# sheet_LAC.net
KiCad netlist of a schematic drawn in Altium Designer
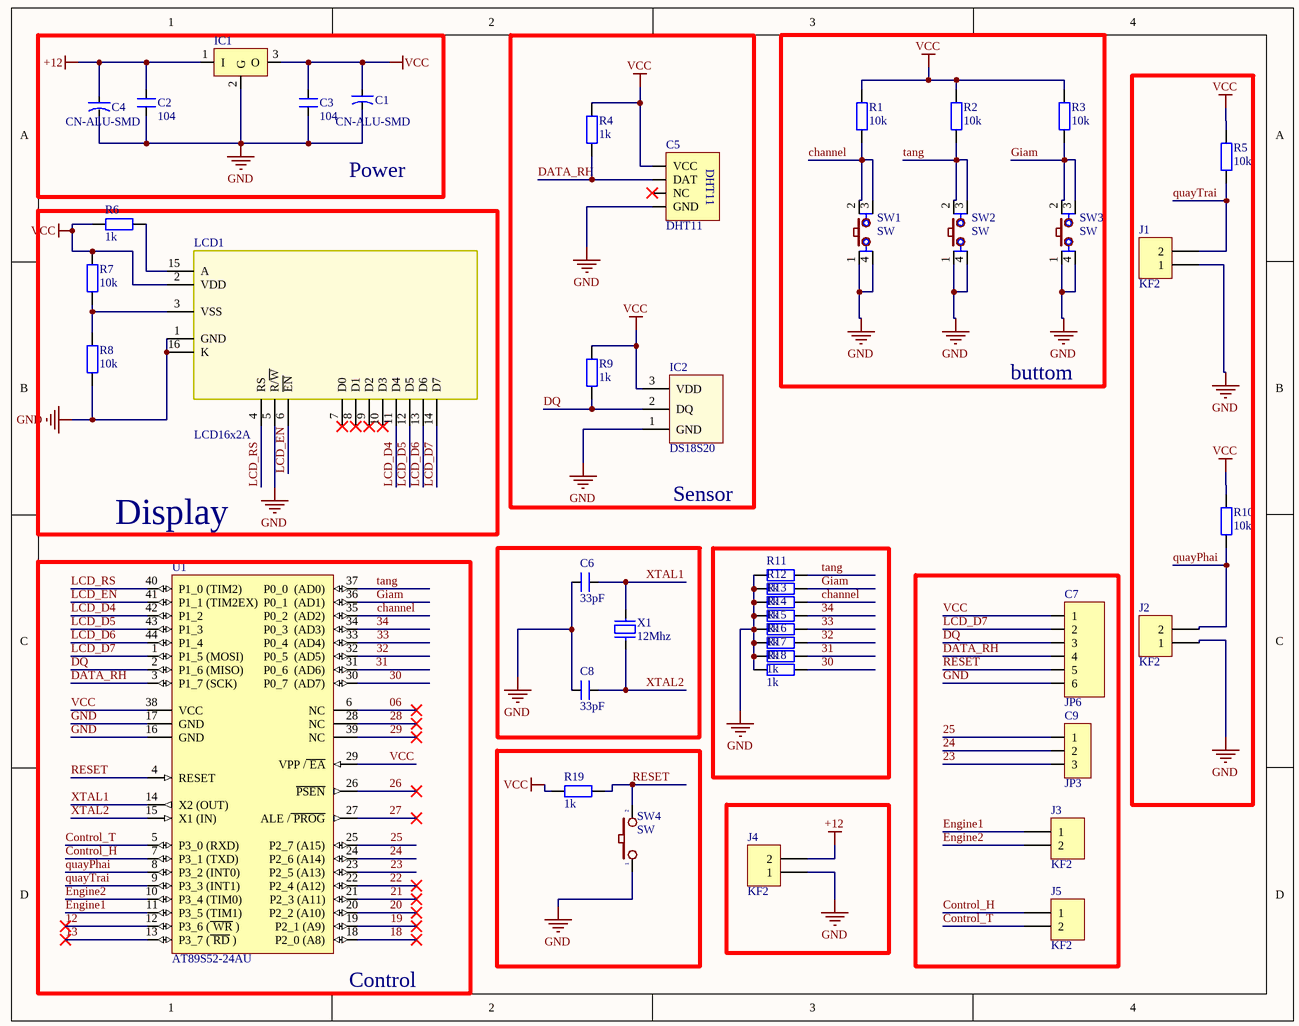
[diagram p0: sheet_LAC.SchDoc]

(export (version "E")
  (design (tool "Eeschema 10.0.6"))
  (components
    (comp (ref "C1")
      (value "CN-ALU-SMD")
      (footprint "3.2X1.6X1.1")
      (description "Polarized Capacitor (Axial)")
      (fields (field (name "PUBLISHER") "Altium Limited"))
      (libsource (lib "LIBRARY") (part "CN-ALU-SMD"))
    )
    (comp (ref "C2")
      (value "104")
      (footprint "SM-CAP-0805")
      (fields (field (name "DESIGNED BY") "VanDungEvn"))
      (libsource (lib "syhaunguyen") (part "CN"))
    )
    (comp (ref "C3")
      (value "104")
      (footprint "SM-CAP-0805")
      (fields (field (name "DESIGNED BY") "VanDungEvn"))
      (libsource (lib "syhaunguyen") (part "CN"))
    )
    (comp (ref "C4")
      (value "CN-ALU-SMD")
      (footprint "3.2X1.6X1.1")
      (description "Polarized Capacitor (Axial)")
      (fields (field (name "PUBLISHER") "Altium Limited"))
      (libsource (lib "LIBRARY") (part "CN-ALU-SMD"))
    )
    (comp (ref "C5")
      (value "DHT11")
      (footprint "DHT11")
      (fields
        (field (name "MANUFACTURER") "Würth Elektronik eiSos GmbH")
        (field (name "PARTNO") "613004143121")
        (field (name "CREATED BY") "Karrer Zheng")
      )
      (libsource (lib "LIBRARY") (part "DHT11"))
    )
    (comp (ref "C6")
      (value "33pF")
      (footprint "6-0805_N")
      (description "Cap np  1pF - 472pF")
      (libsource (lib "syhaunguyen") (part "CN1"))
    )
    (comp (ref "C7")
      (value "JP6")
      (footprint "JP6-C1T")
      (description "WR-PHD 2.54 mm Angled Socket Header")
      (fields
        (field (name "MANUFACTURER") "Würth Elektronik eiSos GmbH")
        (field (name "PARTNO") "613006143121")
        (field (name "CREATED BY") "Karrer Zheng")
      )
      (libsource (lib "LIBRARY") (part "JP6"))
    )
    (comp (ref "C8")
      (value "33pF")
      (footprint "6-0805_N")
      (description "Cap np  1pF - 472pF")
      (libsource (lib "syhaunguyen") (part "CN1"))
    )
    (comp (ref "C9")
      (value "JP3")
      (footprint "JP3-C1T")
      (description "WR-PHD 2.54 mm Angled Socket Header")
      (fields
        (field (name "MANUFACTURER") "Würth Elektronik eiSos GmbH")
        (field (name "PARTNO") "613003143121")
        (field (name "CREATED BY") "Karrer Zheng")
      )
      (libsource (lib "LIBRARY") (part "JP3"))
    )
    (comp (ref "IC1")
      (value "LM78xx")
      (footprint "TO252-123")
      (description "Positive Voltage Regulator")
      (fields (field (name "PUBLISHER") "Altium Limited"))
      (libsource (lib "LIBRARY") (part "LM78xx"))
    )
    (comp (ref "IC2")
      (value "DS18S20")
      (footprint "JP3-C1T")
      (description "High Precision  1-Wire® Digital Thermometer")
      (libsource (lib "LIBRARY") (part "DS18S20"))
    )
    (comp (ref "J1")
      (value "KF2")
      (footprint "KF2-3.5")
      (fields
        (field (name "MANUFACTURER") "Würth Elektronik eiSos GmbH")
        (field (name "PARTNO") "691103110002")
        (field (name "CREATED BY") "Karrer Zheng")
      )
      (libsource (lib "") (part "KF2_1"))
    )
    (comp (ref "J2")
      (value "KF2")
      (footprint "KF2-3.5")
      (fields
        (field (name "MANUFACTURER") "Würth Elektronik eiSos GmbH")
        (field (name "PARTNO") "691103110002")
        (field (name "CREATED BY") "Karrer Zheng")
      )
      (libsource (lib "") (part "KF2_1"))
    )
    (comp (ref "J3")
      (value "KF2")
      (footprint "KF2-3.5")
      (fields
        (field (name "MANUFACTURER") "Würth Elektronik eiSos GmbH")
        (field (name "PARTNO") "691103110002")
        (field (name "CREATED BY") "Karrer Zheng")
      )
      (libsource (lib "LIBRARY") (part "KF2"))
    )
    (comp (ref "J4")
      (value "KF2")
      (footprint "KF2-5.08")
      (fields
        (field (name "MANUFACTURER") "Würth Elektronik eiSos GmbH")
        (field (name "PARTNO") "691103110002")
        (field (name "CREATED BY") "Karrer Zheng")
      )
      (libsource (lib "") (part "KF2_1"))
    )
    (comp (ref "J5")
      (value "KF2")
      (footprint "KF2-3.5")
      (fields
        (field (name "MANUFACTURER") "Würth Elektronik eiSos GmbH")
        (field (name "PARTNO") "691103110002")
        (field (name "CREATED BY") "Karrer Zheng")
      )
      (libsource (lib "LIBRARY") (part "KF2"))
    )
    (comp (ref "LCD1")
      (value "LCD16x2A")
      (footprint "LCD16X2")
      (description "LCD dipslay 16 char, 2 line")
      (libsource (lib "syhaunguyen") (part "LCD16x2"))
    )
    (comp (ref "R1")
      (value "10k")
      (footprint "6-0805_N")
      (description "Resistor 1/4W")
      (libsource (lib "syhaunguyen") (part "R1/4W"))
    )
    (comp (ref "R2")
      (value "10k")
      (footprint "6-0805_N")
      (description "Resistor 1/4W")
      (libsource (lib "syhaunguyen") (part "R1/4W"))
    )
    (comp (ref "R3")
      (value "10k")
      (footprint "6-0805_N")
      (description "Resistor 1/4W")
      (libsource (lib "syhaunguyen") (part "R1/4W"))
    )
    (comp (ref "R4")
      (value "1k")
      (footprint "6-0805_N")
      (description "Resistor 1/4W")
      (libsource (lib "syhaunguyen") (part "R1/4W"))
    )
    (comp (ref "R5")
      (value "10k")
      (footprint "6-0805_N")
      (description "Resistor 1/4W")
      (libsource (lib "syhaunguyen") (part "R1/4W"))
    )
    (comp (ref "R6")
      (value "1k")
      (footprint "6-0805_N")
      (description "Resistor 1/4W")
      (libsource (lib "syhaunguyen") (part "R1/4W"))
    )
    (comp (ref "R7")
      (value "10k")
      (footprint "6-0805_N")
      (description "Resistor 1/4W")
      (libsource (lib "syhaunguyen") (part "R1/4W"))
    )
    (comp (ref "R8")
      (value "10k")
      (footprint "6-0805_N")
      (description "Resistor 1/4W")
      (libsource (lib "syhaunguyen") (part "R1/4W"))
    )
    (comp (ref "R9")
      (value "1k")
      (footprint "6-0805_N")
      (description "Resistor 1/4W")
      (libsource (lib "syhaunguyen") (part "R1/4W"))
    )
    (comp (ref "R10")
      (value "10k")
      (footprint "6-0805_N")
      (description "Resistor 1/4W")
      (libsource (lib "syhaunguyen") (part "R1/4W"))
    )
    (comp (ref "R11")
      (value "1k")
      (footprint "6-0805_N")
      (description "Resistor 1/4W")
      (libsource (lib "syhaunguyen") (part "R1/4W"))
    )
    (comp (ref "R12")
      (value "1k")
      (footprint "6-0805_N")
      (description "Resistor 1/4W")
      (libsource (lib "syhaunguyen") (part "R1/4W"))
    )
    (comp (ref "R13")
      (value "1k")
      (footprint "6-0805_N")
      (description "Resistor 1/4W")
      (libsource (lib "syhaunguyen") (part "R1/4W"))
    )
    (comp (ref "R14")
      (value "1k")
      (footprint "6-0805_N")
      (description "Resistor 1/4W")
      (libsource (lib "syhaunguyen") (part "R1/4W"))
    )
    (comp (ref "R15")
      (value "1k")
      (footprint "6-0805_N")
      (description "Resistor 1/4W")
      (libsource (lib "syhaunguyen") (part "R1/4W"))
    )
    (comp (ref "R16")
      (value "1k")
      (footprint "6-0805_N")
      (description "Resistor 1/4W")
      (libsource (lib "syhaunguyen") (part "R1/4W"))
    )
    (comp (ref "R17")
      (value "1k")
      (footprint "6-0805_N")
      (description "Resistor 1/4W")
      (libsource (lib "syhaunguyen") (part "R1/4W"))
    )
    (comp (ref "R18")
      (value "1k")
      (footprint "6-0805_N")
      (description "Resistor 1/4W")
      (libsource (lib "syhaunguyen") (part "R1/4W"))
    )
    (comp (ref "R19")
      (value "1k")
      (footprint "6-0805_N")
      (description "Resistor 1/4W")
      (libsource (lib "syhaunguyen") (part "R1/4W"))
    )
    (comp (ref "SW1")
      (value "SW")
      (footprint "SW2-DIP")
      (description "Switch button 4 pin")
      (libsource (lib "LIBRARY") (part "SW4"))
    )
    (comp (ref "SW2")
      (value "SW")
      (footprint "SW2-DIP")
      (description "Switch button 4 pin")
      (libsource (lib "LIBRARY") (part "SW4"))
    )
    (comp (ref "SW3")
      (value "SW")
      (footprint "SW2-DIP")
      (description "Switch button 4 pin")
      (libsource (lib "LIBRARY") (part "SW4"))
    )
    (comp (ref "SW4")
      (value "SW")
      (footprint "SW1-SMD")
      (description "Switch button 2 pin")
      (libsource (lib "LIBRARY") (part "SW2"))
    )
    (comp (ref "U1")
      (value "AT89S52-24AU")
      (footprint "TQFP44")
      (description "Atmel 8 Bit Micro 4.0-5.5V 24MHz -40 to +80 Deg C 44TQFP (44A) Package GREEN OPTION")
      (libsource (lib "LIBRARY") (part "AT89S52-24AU"))
    )
    (comp (ref "X1")
      (value "12Mhz")
      (footprint "XT2-SMD")
      (description "Crystal, 32.768 KHz, -40 to 85 degC, 3.2 x 1.5 x 0.9 mm SMD")
      (libsource (lib "LIBRARY") (part "XT2"))
    )
  )
  (nets
    (net (code "1") (name "+12") (class "Default")
      (node (ref "C2") (pin "1") (pinfunction "1_1") (pintype "passive"))
      (node (ref "C4") (pin "1") (pinfunction "1_1") (pintype "passive"))
      (node (ref "IC1") (pin "1") (pinfunction "I_1") (pintype "power_in"))
      (node (ref "J4") (pin "2") (pinfunction "2_2") (pintype "passive"))
    )
    (net (code "2") (name "/06") (class "Default")
      (node (ref "U1") (pin "6") (pinfunction "NC_6") (pintype "passive+no_connect"))
    )
    (net (code "3") (name "/12") (class "Default")
      (node (ref "U1") (pin "12") (pinfunction "P3_6_(~{_WR}_)_12") (pintype "bidirectional+no_connect"))
    )
    (net (code "4") (name "/13") (class "Default")
      (node (ref "U1") (pin "13") (pinfunction "P3_7_(~{_RD}_)_13") (pintype "bidirectional+no_connect"))
    )
    (net (code "5") (name "/18") (class "Default")
      (node (ref "U1") (pin "18") (pinfunction "P2_0_(A8)_18") (pintype "bidirectional+no_connect"))
    )
    (net (code "6") (name "/19") (class "Default")
      (node (ref "U1") (pin "19") (pinfunction "P2_1_(A9)_19") (pintype "bidirectional+no_connect"))
    )
    (net (code "7") (name "/20") (class "Default")
      (node (ref "U1") (pin "20") (pinfunction "P2_2_(A10)_20") (pintype "bidirectional+no_connect"))
    )
    (net (code "8") (name "/21") (class "Default")
      (node (ref "U1") (pin "21") (pinfunction "P2_3_(A11)_21") (pintype "bidirectional+no_connect"))
    )
    (net (code "9") (name "/22") (class "Default")
      (node (ref "U1") (pin "22") (pinfunction "P2_4_(A12)_22") (pintype "bidirectional+no_connect"))
    )
    (net (code "10") (name "/23") (class "Default")
      (node (ref "C9") (pin "3") (pinfunction "3_3") (pintype "passive"))
      (node (ref "U1") (pin "23") (pinfunction "P2_5_(A13)_23") (pintype "bidirectional"))
    )
    (net (code "11") (name "/24") (class "Default")
      (node (ref "C9") (pin "2") (pinfunction "2_2") (pintype "passive"))
      (node (ref "U1") (pin "24") (pinfunction "P2_6_(A14)_24") (pintype "bidirectional"))
    )
    (net (code "12") (name "/25") (class "Default")
      (node (ref "C9") (pin "1") (pinfunction "1_1") (pintype "passive"))
      (node (ref "U1") (pin "25") (pinfunction "P2_7_(A15)_25") (pintype "bidirectional"))
    )
    (net (code "13") (name "/26") (class "Default")
      (node (ref "U1") (pin "26") (pinfunction "PSEN_26") (pintype "output+no_connect"))
    )
    (net (code "14") (name "/27") (class "Default")
      (node (ref "U1") (pin "27") (pinfunction "ALE_/~{_PROG}_27") (pintype "output+no_connect"))
    )
    (net (code "15") (name "/28") (class "Default")
      (node (ref "U1") (pin "28") (pinfunction "NC_28") (pintype "passive+no_connect"))
    )
    (net (code "16") (name "/29") (class "Default")
      (node (ref "U1") (pin "39") (pinfunction "NC_39") (pintype "passive+no_connect"))
    )
    (net (code "17") (name "/30") (class "Default")
      (node (ref "R18") (pin "1") (pinfunction "1_1") (pintype "passive"))
      (node (ref "U1") (pin "30") (pinfunction "P0_7__(AD7)_30") (pintype "bidirectional"))
    )
    (net (code "18") (name "/31") (class "Default")
      (node (ref "R17") (pin "1") (pinfunction "1_1") (pintype "passive"))
      (node (ref "U1") (pin "31") (pinfunction "P0_6__(AD6)_31") (pintype "bidirectional"))
    )
    (net (code "19") (name "/32") (class "Default")
      (node (ref "R16") (pin "1") (pinfunction "1_1") (pintype "passive"))
      (node (ref "U1") (pin "32") (pinfunction "P0_5__(AD5)_32") (pintype "bidirectional"))
    )
    (net (code "20") (name "/33") (class "Default")
      (node (ref "R15") (pin "1") (pinfunction "1_1") (pintype "passive"))
      (node (ref "U1") (pin "33") (pinfunction "P0_4__(AD4)_33") (pintype "bidirectional"))
    )
    (net (code "21") (name "/34") (class "Default")
      (node (ref "R14") (pin "1") (pinfunction "1_1") (pintype "passive"))
      (node (ref "U1") (pin "34") (pinfunction "P0_3__(AD3)_34") (pintype "bidirectional"))
    )
    (net (code "22") (name "/Control_H") (class "Default")
      (node (ref "J5") (pin "1") (pinfunction "1_1") (pintype "passive"))
      (node (ref "U1") (pin "7") (pinfunction "P3_1_(TXD)_7") (pintype "bidirectional"))
    )
    (net (code "23") (name "/Control_T") (class "Default")
      (node (ref "J5") (pin "2") (pinfunction "2_2") (pintype "passive"))
      (node (ref "U1") (pin "5") (pinfunction "P3_0_(RXD)_5") (pintype "bidirectional"))
    )
    (net (code "24") (name "/DATA_RH") (class "Default")
      (node (ref "C5") (pin "2") (pinfunction "DAT_2") (pintype "passive"))
      (node (ref "C7") (pin "4") (pinfunction "4_4") (pintype "passive"))
      (node (ref "R4") (pin "2") (pinfunction "2_2") (pintype "passive"))
      (node (ref "U1") (pin "3") (pinfunction "P1_7_(SCK)_3") (pintype "bidirectional"))
    )
    (net (code "25") (name "/DQ") (class "Default")
      (node (ref "C7") (pin "3") (pinfunction "3_3") (pintype "passive"))
      (node (ref "IC2") (pin "2") (pinfunction "DQ_2") (pintype "passive"))
      (node (ref "R9") (pin "1") (pinfunction "1_1") (pintype "passive"))
      (node (ref "U1") (pin "2") (pinfunction "P1_6_(MISO)_2") (pintype "bidirectional"))
    )
    (net (code "26") (name "/Engine1") (class "Default")
      (node (ref "J3") (pin "1") (pinfunction "1_1") (pintype "passive"))
      (node (ref "U1") (pin "11") (pinfunction "P3_5_(TIM1)_11") (pintype "bidirectional"))
    )
    (net (code "27") (name "/Engine2") (class "Default")
      (node (ref "J3") (pin "2") (pinfunction "2_2") (pintype "passive"))
      (node (ref "U1") (pin "10") (pinfunction "P3_4_(TIM0)_10") (pintype "bidirectional"))
    )
    (net (code "28") (name "/Giam") (class "Default")
      (node (ref "R12") (pin "1") (pinfunction "1_1") (pintype "passive"))
      (node (ref "R3") (pin "2") (pinfunction "2_2") (pintype "passive"))
      (node (ref "SW3") (pin "2") (pinfunction "2_2") (pintype "passive"))
      (node (ref "SW3") (pin "3") (pinfunction "3_3") (pintype "passive"))
      (node (ref "U1") (pin "36") (pinfunction "P0_1__(AD1)_36") (pintype "bidirectional"))
    )
    (net (code "29") (name "/LCD_D4") (class "Default")
      (node (ref "LCD1") (pin "11") (pinfunction "D4_11") (pintype "passive"))
      (node (ref "U1") (pin "42") (pinfunction "P1_2_42") (pintype "bidirectional"))
    )
    (net (code "30") (name "/LCD_D5") (class "Default")
      (node (ref "LCD1") (pin "12") (pinfunction "D5_12") (pintype "passive"))
      (node (ref "U1") (pin "43") (pinfunction "P1_3_43") (pintype "bidirectional"))
    )
    (net (code "31") (name "/LCD_D6") (class "Default")
      (node (ref "LCD1") (pin "13") (pinfunction "D6_13") (pintype "passive"))
      (node (ref "U1") (pin "44") (pinfunction "P1_4_44") (pintype "bidirectional"))
    )
    (net (code "32") (name "/LCD_D7") (class "Default")
      (node (ref "C7") (pin "2") (pinfunction "2_2") (pintype "passive"))
      (node (ref "LCD1") (pin "14") (pinfunction "D7_14") (pintype "passive"))
      (node (ref "U1") (pin "1") (pinfunction "P1_5_(MOSI)_1") (pintype "bidirectional"))
    )
    (net (code "33") (name "/LCD_EN") (class "Default")
      (node (ref "LCD1") (pin "6") (pinfunction "~{EN}_6") (pintype "passive"))
      (node (ref "U1") (pin "41") (pinfunction "P1_1_(TIM2EX)_41") (pintype "bidirectional"))
    )
    (net (code "34") (name "/LCD_RS") (class "Default")
      (node (ref "LCD1") (pin "4") (pinfunction "RS_4") (pintype "passive"))
      (node (ref "U1") (pin "40") (pinfunction "P1_0_(TIM2)_40") (pintype "bidirectional"))
    )
    (net (code "35") (name "/RESET") (class "Default")
      (node (ref "C7") (pin "5") (pinfunction "5_5") (pintype "passive"))
      (node (ref "R19") (pin "1") (pinfunction "1_1") (pintype "passive"))
      (node (ref "SW4") (pin "2") (pinfunction "2_2") (pintype "passive"))
      (node (ref "U1") (pin "4") (pinfunction "RESET_4") (pintype "input"))
    )
    (net (code "36") (name "/XTAL1") (class "Default")
      (node (ref "C6") (pin "2") (pinfunction "2_2") (pintype "passive"))
      (node (ref "U1") (pin "14") (pinfunction "X2_(OUT)_14") (pintype "output"))
      (node (ref "X1") (pin "1") (pinfunction "1_1") (pintype "passive"))
    )
    (net (code "37") (name "/XTAL2") (class "Default")
      (node (ref "C8") (pin "2") (pinfunction "2_2") (pintype "passive"))
      (node (ref "U1") (pin "15") (pinfunction "X1_(IN)_15") (pintype "input"))
      (node (ref "X1") (pin "2") (pinfunction "2_2") (pintype "passive"))
    )
    (net (code "38") (name "/channel") (class "Default")
      (node (ref "R1") (pin "2") (pinfunction "2_2") (pintype "passive"))
      (node (ref "R13") (pin "1") (pinfunction "1_1") (pintype "passive"))
      (node (ref "SW1") (pin "2") (pinfunction "2_2") (pintype "passive"))
      (node (ref "SW1") (pin "3") (pinfunction "3_3") (pintype "passive"))
      (node (ref "U1") (pin "35") (pinfunction "P0_2__(AD2)_35") (pintype "bidirectional"))
    )
    (net (code "39") (name "/quayPhai") (class "Default")
      (node (ref "J2") (pin "2") (pinfunction "2_2") (pintype "passive"))
      (node (ref "R10") (pin "2") (pinfunction "2_2") (pintype "passive"))
      (node (ref "U1") (pin "8") (pinfunction "P3_2_(INT0)_8") (pintype "bidirectional"))
    )
    (net (code "40") (name "/quayTrai") (class "Default")
      (node (ref "J1") (pin "2") (pinfunction "2_2") (pintype "passive"))
      (node (ref "R5") (pin "2") (pinfunction "2_2") (pintype "passive"))
      (node (ref "U1") (pin "9") (pinfunction "P3_3_(INT1)_9") (pintype "bidirectional"))
    )
    (net (code "41") (name "/tang") (class "Default")
      (node (ref "R11") (pin "1") (pinfunction "1_1") (pintype "passive"))
      (node (ref "R2") (pin "2") (pinfunction "2_2") (pintype "passive"))
      (node (ref "SW2") (pin "2") (pinfunction "2_2") (pintype "passive"))
      (node (ref "SW2") (pin "3") (pinfunction "3_3") (pintype "passive"))
      (node (ref "U1") (pin "37") (pinfunction "P0_0__(AD0)_37") (pintype "bidirectional"))
    )
    (net (code "42") (name "GND") (class "Default")
      (node (ref "C1") (pin "2") (pinfunction "2_2") (pintype "passive"))
      (node (ref "C2") (pin "2") (pinfunction "2_2") (pintype "passive"))
      (node (ref "C3") (pin "2") (pinfunction "2_2") (pintype "passive"))
      (node (ref "C4") (pin "2") (pinfunction "2_2") (pintype "passive"))
      (node (ref "C5") (pin "4") (pinfunction "GND_4") (pintype "passive"))
      (node (ref "C6") (pin "1") (pinfunction "1_1") (pintype "passive"))
      (node (ref "C7") (pin "6") (pinfunction "6_6") (pintype "passive"))
      (node (ref "C8") (pin "1") (pinfunction "1_1") (pintype "passive"))
      (node (ref "IC1") (pin "2") (pinfunction "G_2") (pintype "power_in"))
      (node (ref "IC2") (pin "1") (pinfunction "GND_1") (pintype "passive"))
      (node (ref "J1") (pin "1") (pinfunction "1_1") (pintype "passive"))
      (node (ref "J2") (pin "1") (pinfunction "1_1") (pintype "passive"))
      (node (ref "J4") (pin "1") (pinfunction "1_1") (pintype "passive"))
      (node (ref "LCD1") (pin "1") (pinfunction "GND_1") (pintype "passive"))
      (node (ref "LCD1") (pin "16") (pinfunction "K_16") (pintype "passive"))
      (node (ref "LCD1") (pin "5") (pinfunction "R/~{W}_5") (pintype "passive"))
      (node (ref "R11") (pin "2") (pinfunction "2_2") (pintype "passive"))
      (node (ref "R12") (pin "2") (pinfunction "2_2") (pintype "passive"))
      (node (ref "R13") (pin "2") (pinfunction "2_2") (pintype "passive"))
      (node (ref "R14") (pin "2") (pinfunction "2_2") (pintype "passive"))
      (node (ref "R15") (pin "2") (pinfunction "2_2") (pintype "passive"))
      (node (ref "R16") (pin "2") (pinfunction "2_2") (pintype "passive"))
      (node (ref "R17") (pin "2") (pinfunction "2_2") (pintype "passive"))
      (node (ref "R18") (pin "2") (pinfunction "2_2") (pintype "passive"))
      (node (ref "R8") (pin "2") (pinfunction "2_2") (pintype "passive"))
      (node (ref "SW1") (pin "1") (pintype "passive"))
      (node (ref "SW1") (pin "4") (pinfunction "4_4") (pintype "passive"))
      (node (ref "SW2") (pin "1") (pintype "passive"))
      (node (ref "SW2") (pin "4") (pinfunction "4_4") (pintype "passive"))
      (node (ref "SW3") (pin "1") (pintype "passive"))
      (node (ref "SW3") (pin "4") (pinfunction "4_4") (pintype "passive"))
      (node (ref "SW4") (pin "1") (pinfunction "1_1") (pintype "passive"))
      (node (ref "U1") (pin "16") (pinfunction "GND_16") (pintype "power_in"))
      (node (ref "U1") (pin "17") (pinfunction "GND_17") (pintype "power_in"))
    )
    (net (code "43") (name "Net-(LCD1-A)") (class "Default")
      (node (ref "LCD1") (pin "15") (pinfunction "A_15") (pintype "passive"))
      (node (ref "R6") (pin "2") (pinfunction "2_2") (pintype "passive"))
    )
    (net (code "44") (name "Net-(LCD1-VSS)") (class "Default")
      (node (ref "LCD1") (pin "3") (pinfunction "VSS_3") (pintype "passive"))
      (node (ref "R7") (pin "2") (pinfunction "2_2") (pintype "passive"))
      (node (ref "R8") (pin "1") (pinfunction "1_1") (pintype "passive"))
    )
    (net (code "45") (name "VCC") (class "Default")
      (node (ref "C1") (pin "1") (pinfunction "1_1") (pintype "passive"))
      (node (ref "C3") (pin "1") (pinfunction "1_1") (pintype "passive"))
      (node (ref "C5") (pin "1") (pinfunction "VCC_1") (pintype "passive"))
      (node (ref "C7") (pin "1") (pinfunction "1_1") (pintype "passive"))
      (node (ref "IC1") (pin "3") (pinfunction "O_3") (pintype "power_in"))
      (node (ref "IC2") (pin "3") (pinfunction "VDD_3") (pintype "passive"))
      (node (ref "LCD1") (pin "2") (pinfunction "VDD_2") (pintype "passive"))
      (node (ref "R1") (pin "1") (pinfunction "1_1") (pintype "passive"))
      (node (ref "R10") (pin "1") (pinfunction "1_1") (pintype "passive"))
      (node (ref "R19") (pin "2") (pinfunction "2_2") (pintype "passive"))
      (node (ref "R2") (pin "1") (pinfunction "1_1") (pintype "passive"))
      (node (ref "R3") (pin "1") (pinfunction "1_1") (pintype "passive"))
      (node (ref "R4") (pin "1") (pinfunction "1_1") (pintype "passive"))
      (node (ref "R5") (pin "1") (pinfunction "1_1") (pintype "passive"))
      (node (ref "R6") (pin "1") (pinfunction "1_1") (pintype "passive"))
      (node (ref "R7") (pin "1") (pinfunction "1_1") (pintype "passive"))
      (node (ref "R9") (pin "2") (pinfunction "2_2") (pintype "passive"))
      (node (ref "U1") (pin "29") (pinfunction "VPP_/~{_EA}_29") (pintype "input"))
      (node (ref "U1") (pin "38") (pinfunction "VCC_38") (pintype "power_in"))
    )
    (net (code "46") (name "unconnected-(C5-NC-Pad3)") (class "Default")
      (node (ref "C5") (pin "3") (pinfunction "NC_3") (pintype "passive+no_connect"))
    )
    (net (code "47") (name "unconnected-(LCD1-D0-Pad7)") (class "Default")
      (node (ref "LCD1") (pin "7") (pinfunction "D0_7") (pintype "passive+no_connect"))
    )
    (net (code "48") (name "unconnected-(LCD1-D1-Pad8)") (class "Default")
      (node (ref "LCD1") (pin "8") (pinfunction "D1_8") (pintype "passive+no_connect"))
    )
    (net (code "49") (name "unconnected-(LCD1-D2-Pad9)") (class "Default")
      (node (ref "LCD1") (pin "9") (pinfunction "D2_9") (pintype "passive+no_connect"))
    )
    (net (code "50") (name "unconnected-(LCD1-D3-Pad10)") (class "Default")
      (node (ref "LCD1") (pin "10") (pinfunction "D3_10") (pintype "passive+no_connect"))
    )
  )
)
